# Schematic_Altium.net
KiCad netlist of a schematic drawn in Altium Designer
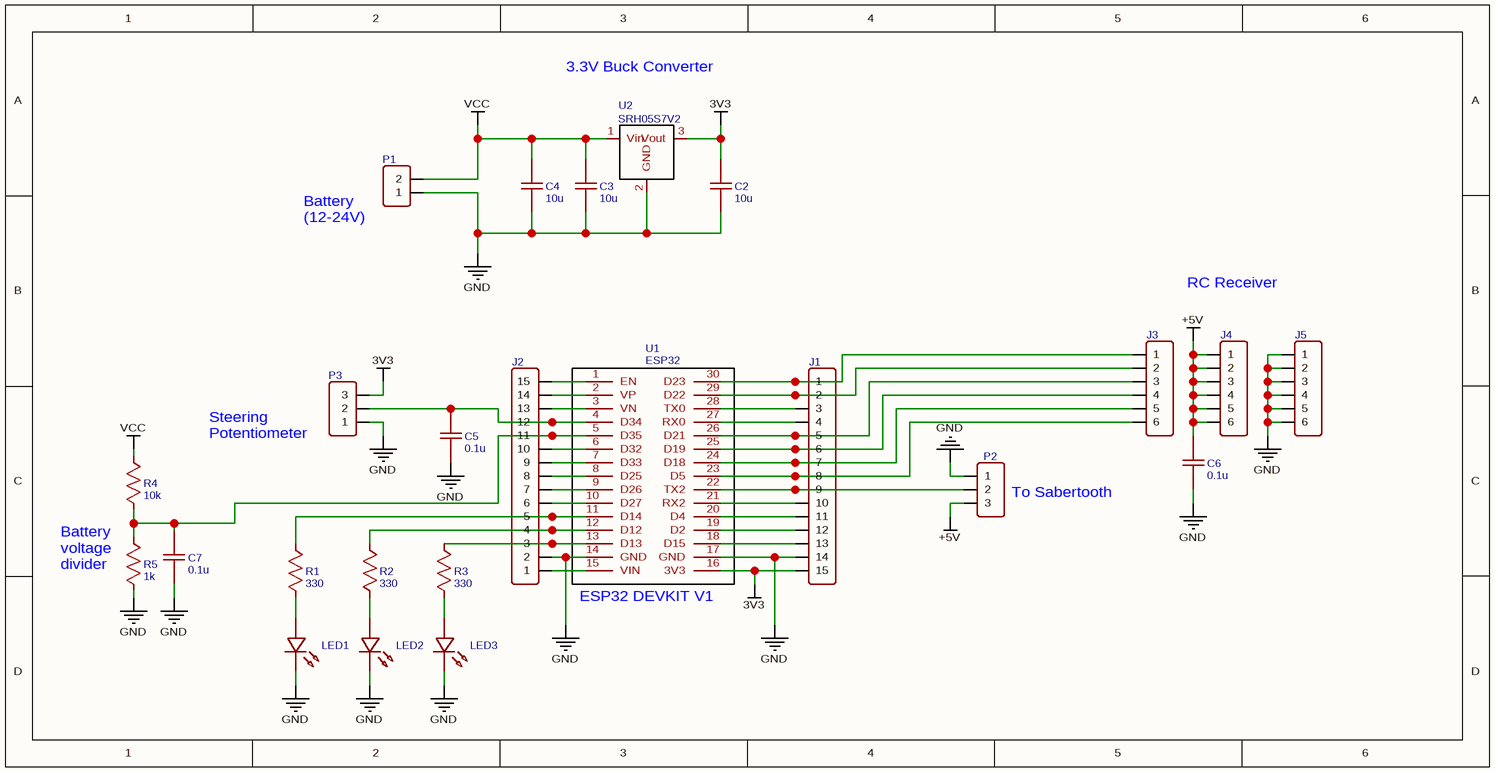
[diagram p0: Schematic_Altium.schdoc]

(export (version "E")
  (design (tool "Eeschema 10.0.6"))
  (components
    (comp (ref "C2")
      (value "10u")
      (fields (field (name "BOM_SUPPLIER PART") "1276-6736-1-ND") (field (name "CONTRIBUTOR") "LCEDA_Lib"))
      (libsource (lib "altium-import") (part "root_1_10u_"))
    )
    (comp (ref "C3")
      (value "10u")
      (fields (field (name "BOM_SUPPLIER PART") "1276-6736-1-ND") (field (name "CONTRIBUTOR") "LCEDA_Lib"))
      (libsource (lib "altium-import") (part "root_1_10u_"))
    )
    (comp (ref "C4")
      (value "10u")
      (fields (field (name "BOM_SUPPLIER PART") "1276-6736-1-ND") (field (name "CONTRIBUTOR") "LCEDA_Lib"))
      (libsource (lib "altium-import") (part "root_1_10u_"))
    )
    (comp (ref "C5")
      (value "0.1u")
      (fields (field (name "CONTRIBUTOR") "LCEDA_Lib"))
      (libsource (lib "altium-import") (part "root_1_0.1u_"))
    )
    (comp (ref "C6")
      (value "0.1u")
      (fields (field (name "CONTRIBUTOR") "LCEDA_Lib"))
      (libsource (lib "altium-import") (part "root_1_0.1u_"))
    )
    (comp (ref "C7")
      (value "0.1u")
      (fields (field (name "CONTRIBUTOR") "LCEDA_Lib"))
      (libsource (lib "altium-import") (part "root_1_0.1u_"))
    )
    (comp (ref "J1")
      (value "HDR-M-2.54_1x15")
      (fields (field (name "BOM_SUPPLIER PART") "C124373") (field (name "CONTRIBUTOR") "LCEDA_Lib"))
      (libsource (lib "altium-import") (part "root_0_HDR-M-2.54_1x15_"))
    )
    (comp (ref "J2")
      (value "HDR-M-2.54_1x15")
      (fields (field (name "BOM_SUPPLIER PART") "C124373") (field (name "CONTRIBUTOR") "LCEDA_Lib"))
      (libsource (lib "altium-import") (part "root_2_HDR-M-2.54_1x15_"))
    )
    (comp (ref "J3")
      (value "HDR-M-2.54_1x6")
      (fields (field (name "BOM_SUPPLIER PART") "C190819") (field (name "CONTRIBUTOR") "LCEDA_Lib"))
      (libsource (lib "altium-import") (part "root_0_HDR-M-2.54_1x6_"))
    )
    (comp (ref "J4")
      (value "HDR-M-2.54_1x6")
      (fields (field (name "BOM_SUPPLIER PART") "C190819") (field (name "CONTRIBUTOR") "LCEDA_Lib"))
      (libsource (lib "altium-import") (part "root_0_HDR-M-2.54_1x6_"))
    )
    (comp (ref "J5")
      (value "HDR-M-2.54_1x6")
      (fields (field (name "BOM_SUPPLIER PART") "C190819") (field (name "CONTRIBUTOR") "LCEDA_Lib"))
      (libsource (lib "altium-import") (part "root_0_HDR-M-2.54_1x6_"))
    )
    (comp (ref "LED1")
      (value "LED-TH-3mm_R")
      (fields
        (field (name "BOM_MANUFACTURER PART") "204-10SDRD/S530-A3-L")
        (field (name "BOM_SUPPLIER PART") "C84774")
        (field (name "CONTRIBUTOR") "LCEDA_Lib")
      )
      (libsource (lib "altium-import") (part "root_3_LED-TH-3mm_R_"))
    )
    (comp (ref "LED2")
      (value "LED-TH-3mm_R")
      (fields
        (field (name "BOM_MANUFACTURER PART") "204-10SDRD/S530-A3-L")
        (field (name "BOM_SUPPLIER PART") "C84774")
        (field (name "CONTRIBUTOR") "LCEDA_Lib")
      )
      (libsource (lib "altium-import") (part "root_3_LED-TH-3mm_R_"))
    )
    (comp (ref "LED3")
      (value "LED-TH-3mm_R")
      (fields
        (field (name "BOM_MANUFACTURER PART") "204-10SDRD/S530-A3-L")
        (field (name "BOM_SUPPLIER PART") "C84774")
        (field (name "CONTRIBUTOR") "LCEDA_Lib")
      )
      (libsource (lib "altium-import") (part "root_3_LED-TH-3mm_R_"))
    )
    (comp (ref "P1")
      (value "CONN-TH_2P-P5.00")
      (fields (field (name "CONTRIBUTOR") "LCEDA_Lib"))
      (libsource (lib "altium-import") (part "root_2_CONN-TH_2P-P5.00_"))
    )
    (comp (ref "P2")
      (value "CONN-TH_3P-P5.00")
      (fields (field (name "CONTRIBUTOR") "LCEDA_Lib"))
      (libsource (lib "altium-import") (part "root_0_CONN-TH_3P-P5.00_"))
    )
    (comp (ref "P3")
      (value "CONN-TH_3P-P5.00")
      (fields (field (name "CONTRIBUTOR") "LCEDA_Lib"))
      (libsource (lib "altium-import") (part "root_2_CONN-TH_3P-P5.00_"))
    )
    (comp (ref "R1")
      (value "330")
      (fields (field (name "CONTRIBUTOR") "LCEDA_Lib"))
      (libsource (lib "altium-import") (part "root_1_330_"))
    )
    (comp (ref "R2")
      (value "330")
      (fields (field (name "CONTRIBUTOR") "LCEDA_Lib"))
      (libsource (lib "altium-import") (part "root_1_330_"))
    )
    (comp (ref "R3")
      (value "330")
      (fields (field (name "CONTRIBUTOR") "LCEDA_Lib"))
      (libsource (lib "altium-import") (part "root_1_330_"))
    )
    (comp (ref "R4")
      (value "10k")
      (fields (field (name "CONTRIBUTOR") "LCEDA_Lib"))
      (libsource (lib "altium-import") (part "root_1_10k_"))
    )
    (comp (ref "R5")
      (value "1k")
      (fields (field (name "CONTRIBUTOR") "LCEDA_Lib"))
      (libsource (lib "altium-import") (part "root_1_1k_"))
    )
    (comp (ref "U1")
      (value "ESP32")
      (fields (field (name "CONTRIBUTOR") "philipp.maack"))
      (libsource (lib "altium-import") (part "root_0_ESP32_"))
    )
    (comp (ref "U2")
      (value "SRH05S7V2")
      (fields
        (field (name "BOM_SUPPLIER PART") "174-4675")
        (field (name "CONTRIBUTOR") "AleksejsSkorodumovs")
      )
      (libsource (lib "altium-import") (part "root_0_SRH05S7V2_"))
    )
  )
  (nets
    (net (code "1") (name "+5V") (class "Default")
      (node (ref "C6") (pin "2") (pinfunction "2_2") (pintype "passive"))
      (node (ref "J4") (pin "1") (pinfunction "1_1") (pintype "passive"))
      (node (ref "J4") (pin "2") (pinfunction "2_2") (pintype "passive"))
      (node (ref "J4") (pin "3") (pinfunction "3_3") (pintype "passive"))
      (node (ref "J4") (pin "4") (pinfunction "4_4") (pintype "passive"))
      (node (ref "J4") (pin "5") (pinfunction "5_5") (pintype "passive"))
      (node (ref "J4") (pin "6") (pinfunction "6_6") (pintype "passive"))
      (node (ref "P2") (pin "3") (pinfunction "3_3") (pintype "passive"))
    )
    (net (code "2") (name "3V3") (class "Default")
      (node (ref "C2") (pin "2") (pinfunction "2_2") (pintype "passive"))
      (node (ref "J1") (pin "15") (pinfunction "15_15") (pintype "passive"))
      (node (ref "P3") (pin "3") (pinfunction "3_3") (pintype "passive"))
      (node (ref "U1") (pin "16") (pinfunction "3V3_16") (pintype "passive"))
      (node (ref "U2") (pin "3") (pinfunction "Vout_3") (pintype "passive"))
    )
    (net (code "3") (name "GND") (class "Default")
      (node (ref "C2") (pin "1") (pinfunction "1_1") (pintype "passive"))
      (node (ref "C3") (pin "1") (pinfunction "1_1") (pintype "passive"))
      (node (ref "C4") (pin "1") (pinfunction "1_1") (pintype "passive"))
      (node (ref "C5") (pin "1") (pinfunction "1_1") (pintype "passive"))
      (node (ref "C6") (pin "1") (pinfunction "1_1") (pintype "passive"))
      (node (ref "C7") (pin "1") (pinfunction "1_1") (pintype "passive"))
      (node (ref "J1") (pin "14") (pinfunction "14_14") (pintype "passive"))
      (node (ref "J2") (pin "2") (pinfunction "2_2") (pintype "passive"))
      (node (ref "J5") (pin "1") (pinfunction "1_1") (pintype "passive"))
      (node (ref "J5") (pin "2") (pinfunction "2_2") (pintype "passive"))
      (node (ref "J5") (pin "3") (pinfunction "3_3") (pintype "passive"))
      (node (ref "J5") (pin "4") (pinfunction "4_4") (pintype "passive"))
      (node (ref "J5") (pin "5") (pinfunction "5_5") (pintype "passive"))
      (node (ref "J5") (pin "6") (pinfunction "6_6") (pintype "passive"))
      (node (ref "LED1") (pin "2") (pinfunction "2_2") (pintype "passive"))
      (node (ref "LED2") (pin "2") (pinfunction "2_2") (pintype "passive"))
      (node (ref "LED3") (pin "2") (pinfunction "2_2") (pintype "passive"))
      (node (ref "P1") (pin "1") (pinfunction "1_1") (pintype "passive"))
      (node (ref "P2") (pin "1") (pinfunction "1_1") (pintype "passive"))
      (node (ref "P3") (pin "1") (pinfunction "1_1") (pintype "passive"))
      (node (ref "R5") (pin "1") (pinfunction "1_1") (pintype "passive"))
      (node (ref "U1") (pin "14") (pinfunction "GND_14") (pintype "passive"))
      (node (ref "U1") (pin "17") (pinfunction "GND_17") (pintype "passive"))
      (node (ref "U2") (pin "2") (pinfunction "GND_2") (pintype "passive"))
    )
    (net (code "4") (name "Net-(LED1-Pad1)") (class "Default")
      (node (ref "LED1") (pin "1") (pinfunction "1_1") (pintype "passive"))
      (node (ref "R1") (pin "1") (pinfunction "1_1") (pintype "passive"))
    )
    (net (code "5") (name "Net-(LED2-Pad1)") (class "Default")
      (node (ref "LED2") (pin "1") (pinfunction "1_1") (pintype "passive"))
      (node (ref "R2") (pin "1") (pinfunction "1_1") (pintype "passive"))
    )
    (net (code "6") (name "Net-(LED3-Pad1)") (class "Default")
      (node (ref "LED3") (pin "1") (pinfunction "1_1") (pintype "passive"))
      (node (ref "R3") (pin "1") (pinfunction "1_1") (pintype "passive"))
    )
    (net (code "7") (name "Net-(U1-D2)") (class "Default")
      (node (ref "J1") (pin "12") (pinfunction "12_12") (pintype "passive"))
      (node (ref "U1") (pin "19") (pinfunction "D2_19") (pintype "passive"))
    )
    (net (code "8") (name "Net-(U1-D4)") (class "Default")
      (node (ref "J1") (pin "11") (pinfunction "11_11") (pintype "passive"))
      (node (ref "U1") (pin "20") (pinfunction "D4_20") (pintype "passive"))
    )
    (net (code "9") (name "Net-(U1-D5)") (class "Default")
      (node (ref "J1") (pin "8") (pinfunction "8_8") (pintype "passive"))
      (node (ref "J3") (pin "6") (pinfunction "6_6") (pintype "passive"))
      (node (ref "U1") (pin "23") (pinfunction "D5_23") (pintype "passive"))
    )
    (net (code "10") (name "Net-(U1-D12)") (class "Default")
      (node (ref "J2") (pin "4") (pinfunction "4_4") (pintype "passive"))
      (node (ref "R2") (pin "2") (pinfunction "2_2") (pintype "passive"))
      (node (ref "U1") (pin "12") (pinfunction "D12_12") (pintype "passive"))
    )
    (net (code "11") (name "Net-(U1-D13)") (class "Default")
      (node (ref "J2") (pin "3") (pinfunction "3_3") (pintype "passive"))
      (node (ref "R3") (pin "2") (pinfunction "2_2") (pintype "passive"))
      (node (ref "U1") (pin "13") (pinfunction "D13_13") (pintype "passive"))
    )
    (net (code "12") (name "Net-(U1-D14)") (class "Default")
      (node (ref "J2") (pin "5") (pinfunction "5_5") (pintype "passive"))
      (node (ref "R1") (pin "2") (pinfunction "2_2") (pintype "passive"))
      (node (ref "U1") (pin "11") (pinfunction "D14_11") (pintype "passive"))
    )
    (net (code "13") (name "Net-(U1-D15)") (class "Default")
      (node (ref "J1") (pin "13") (pinfunction "13_13") (pintype "passive"))
      (node (ref "U1") (pin "18") (pinfunction "D15_18") (pintype "passive"))
    )
    (net (code "14") (name "Net-(U1-D18)") (class "Default")
      (node (ref "J1") (pin "7") (pinfunction "7_7") (pintype "passive"))
      (node (ref "J3") (pin "5") (pinfunction "5_5") (pintype "passive"))
      (node (ref "U1") (pin "24") (pinfunction "D18_24") (pintype "passive"))
    )
    (net (code "15") (name "Net-(U1-D19)") (class "Default")
      (node (ref "J1") (pin "6") (pinfunction "6_6") (pintype "passive"))
      (node (ref "J3") (pin "4") (pinfunction "4_4") (pintype "passive"))
      (node (ref "U1") (pin "25") (pinfunction "D19_25") (pintype "passive"))
    )
    (net (code "16") (name "Net-(U1-D21)") (class "Default")
      (node (ref "J1") (pin "5") (pinfunction "5_5") (pintype "passive"))
      (node (ref "J3") (pin "3") (pinfunction "3_3") (pintype "passive"))
      (node (ref "U1") (pin "26") (pinfunction "D21_26") (pintype "passive"))
    )
    (net (code "17") (name "Net-(U1-D22)") (class "Default")
      (node (ref "J1") (pin "2") (pinfunction "2_2") (pintype "passive"))
      (node (ref "J3") (pin "2") (pinfunction "2_2") (pintype "passive"))
      (node (ref "U1") (pin "29") (pinfunction "D22_29") (pintype "passive"))
    )
    (net (code "18") (name "Net-(U1-D23)") (class "Default")
      (node (ref "J1") (pin "1") (pinfunction "1_1") (pintype "passive"))
      (node (ref "J3") (pin "1") (pinfunction "1_1") (pintype "passive"))
      (node (ref "U1") (pin "30") (pinfunction "D23_30") (pintype "passive"))
    )
    (net (code "19") (name "Net-(U1-D25)") (class "Default")
      (node (ref "J2") (pin "8") (pinfunction "8_8") (pintype "passive"))
      (node (ref "U1") (pin "8") (pinfunction "D25_8") (pintype "passive"))
    )
    (net (code "20") (name "Net-(U1-D26)") (class "Default")
      (node (ref "J2") (pin "7") (pinfunction "7_7") (pintype "passive"))
      (node (ref "U1") (pin "9") (pinfunction "D26_9") (pintype "passive"))
    )
    (net (code "21") (name "Net-(U1-D27)") (class "Default")
      (node (ref "J2") (pin "6") (pinfunction "6_6") (pintype "passive"))
      (node (ref "U1") (pin "10") (pinfunction "D27_10") (pintype "passive"))
    )
    (net (code "22") (name "Net-(U1-D32)") (class "Default")
      (node (ref "J2") (pin "10") (pinfunction "10_10") (pintype "passive"))
      (node (ref "U1") (pin "6") (pinfunction "D32_6") (pintype "passive"))
    )
    (net (code "23") (name "Net-(U1-D33)") (class "Default")
      (node (ref "J2") (pin "9") (pinfunction "9_9") (pintype "passive"))
      (node (ref "U1") (pin "7") (pinfunction "D33_7") (pintype "passive"))
    )
    (net (code "24") (name "Net-(U1-D34)") (class "Default")
      (node (ref "C5") (pin "2") (pinfunction "2_2") (pintype "passive"))
      (node (ref "J2") (pin "12") (pinfunction "12_12") (pintype "passive"))
      (node (ref "P3") (pin "2") (pinfunction "2_2") (pintype "passive"))
      (node (ref "U1") (pin "4") (pinfunction "D34_4") (pintype "passive"))
    )
    (net (code "25") (name "Net-(U1-D35)") (class "Default")
      (node (ref "C7") (pin "2") (pinfunction "2_2") (pintype "passive"))
      (node (ref "J2") (pin "11") (pinfunction "11_11") (pintype "passive"))
      (node (ref "R4") (pin "1") (pinfunction "1_1") (pintype "passive"))
      (node (ref "R5") (pin "2") (pinfunction "2_2") (pintype "passive"))
      (node (ref "U1") (pin "5") (pinfunction "D35_5") (pintype "passive"))
    )
    (net (code "26") (name "Net-(U1-EN)") (class "Default")
      (node (ref "J2") (pin "15") (pinfunction "15_15") (pintype "passive"))
      (node (ref "U1") (pin "1") (pinfunction "EN_1") (pintype "passive"))
    )
    (net (code "27") (name "Net-(U1-RX0)") (class "Default")
      (node (ref "J1") (pin "4") (pinfunction "4_4") (pintype "passive"))
      (node (ref "U1") (pin "27") (pinfunction "RX0_27") (pintype "passive"))
    )
    (net (code "28") (name "Net-(U1-RX2)") (class "Default")
      (node (ref "J1") (pin "10") (pinfunction "10_10") (pintype "passive"))
      (node (ref "U1") (pin "21") (pinfunction "RX2_21") (pintype "passive"))
    )
    (net (code "29") (name "Net-(U1-TX0)") (class "Default")
      (node (ref "J1") (pin "3") (pinfunction "3_3") (pintype "passive"))
      (node (ref "U1") (pin "28") (pinfunction "TX0_28") (pintype "passive"))
    )
    (net (code "30") (name "Net-(U1-TX2)") (class "Default")
      (node (ref "J1") (pin "9") (pinfunction "9_9") (pintype "passive"))
      (node (ref "P2") (pin "2") (pinfunction "2_2") (pintype "passive"))
      (node (ref "U1") (pin "22") (pinfunction "TX2_22") (pintype "passive"))
    )
    (net (code "31") (name "Net-(U1-VIN)") (class "Default")
      (node (ref "J2") (pin "1") (pinfunction "1_1") (pintype "passive"))
      (node (ref "U1") (pin "15") (pinfunction "VIN_15") (pintype "passive"))
    )
    (net (code "32") (name "Net-(U1-VN)") (class "Default")
      (node (ref "J2") (pin "13") (pinfunction "13_13") (pintype "passive"))
      (node (ref "U1") (pin "3") (pinfunction "VN_3") (pintype "passive"))
    )
    (net (code "33") (name "Net-(U1-VP)") (class "Default")
      (node (ref "J2") (pin "14") (pinfunction "14_14") (pintype "passive"))
      (node (ref "U1") (pin "2") (pinfunction "VP_2") (pintype "passive"))
    )
    (net (code "34") (name "VCC") (class "Default")
      (node (ref "C3") (pin "2") (pinfunction "2_2") (pintype "passive"))
      (node (ref "C4") (pin "2") (pinfunction "2_2") (pintype "passive"))
      (node (ref "P1") (pin "2") (pinfunction "2_2") (pintype "passive"))
      (node (ref "R4") (pin "2") (pinfunction "2_2") (pintype "passive"))
      (node (ref "U2") (pin "1") (pinfunction "Vin_1") (pintype "passive"))
    )
  )
)
